# Main.net
KiCad netlist of a schematic drawn in EAGLE
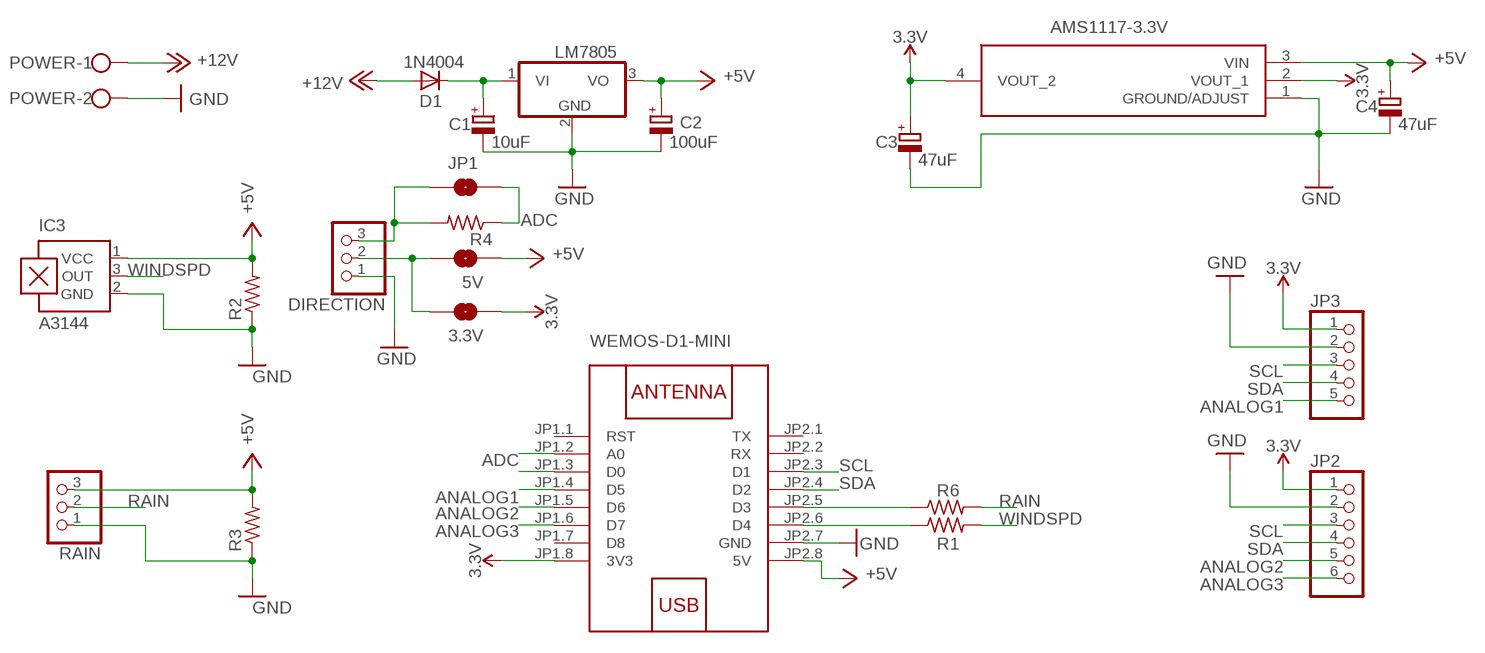
[diagram p0: schematic, sheet 1]

(export (version "E")
  (design (tool "Eeschema 10.0.6"))
  (components
    (comp (ref "3.3V")
      (value "JUMPER-SMT_2_NO_NO-SILK")
      (footprint "eagle-import:SMT-JUMPER_2_NO_NO-SILK")
      (libsource (lib "eagle-import") (part "JUMPER-SMT_2_NO_NO-SILK"))
    )
    (comp (ref "5V")
      (value "JUMPER-SMT_2_NO_NO-SILK")
      (footprint "eagle-import:SMT-JUMPER_2_NO_NO-SILK")
      (libsource (lib "eagle-import") (part "JUMPER-SMT_2_NO_NO-SILK"))
    )
    (comp (ref "C1")
      (value "10uF")
      (footprint "eagle-import:E2,5-5")
      (libsource (lib "eagle-import") (part "CPOL-EUE2.5-5"))
    )
    (comp (ref "C2")
      (value "100uF")
      (footprint "eagle-import:E2,5-5")
      (libsource (lib "eagle-import") (part "CPOL-EUE2.5-5"))
    )
    (comp (ref "C3")
      (value "47uF")
      (footprint "eagle-import:E2,5-5")
      (libsource (lib "eagle-import") (part "CPOL-EUE2.5-5"))
    )
    (comp (ref "C4")
      (value "47uF")
      (footprint "eagle-import:E2,5-5")
      (libsource (lib "eagle-import") (part "CPOL-EUE2.5-5"))
    )
    (comp (ref "D1")
      (value "1N4004")
      (footprint "eagle-import:DO41-10")
      (libsource (lib "eagle-import") (part "1N4004"))
    )
    (comp (ref "DIRECTION")
      (value "PINHD-1X3/90")
      (footprint "eagle-import:1X03_90")
      (libsource (lib "eagle-import") (part "PINHD-1X3/90"))
    )
    (comp (ref "IC1")
      (value "LM7805")
      (footprint "eagle-import:TO220H")
      (libsource (lib "eagle-import") (part "78T05"))
    )
    (comp (ref "IC2")
      (value "AMS1117-3.3V")
      (footprint "eagle-import:SOT229P700X180-4N")
      (fields (field (name "MANUFACTURER_PART_NUMBER") "ams1117-3.3v"))
      (libsource (lib "eagle-import") (part "AMS1117-3.3V"))
    )
    (comp (ref "IC3")
      (value "A3144")
      (footprint "eagle-import:SIP3-UA")
      (fields (field (name "MF") "ALLEGRO MICROSYSTEMS, INC.") (field (name "MPN") "A1301EUA-T"))
      (libsource (lib "eagle-import") (part "A13?UA01"))
    )
    (comp (ref "JP1")
      (value "JUMPER-SMT_2_NO_NO-SILK")
      (footprint "eagle-import:SMT-JUMPER_2_NO_NO-SILK")
      (libsource (lib "eagle-import") (part "JUMPER-SMT_2_NO_NO-SILK"))
    )
    (comp (ref "JP2")
      (value "PINHD-1X6/90")
      (footprint "eagle-import:1X06_90")
      (libsource (lib "eagle-import") (part "PINHD-1X6/90"))
    )
    (comp (ref "JP3")
      (value "PINHD-1X5/90")
      (footprint "eagle-import:1X05_90")
      (libsource (lib "eagle-import") (part "PINHD-1X5/90"))
    )
    (comp (ref "POWER")
      (value "W237-102")
      (footprint "eagle-import:W237-102")
      (fields (field (name "MPN") "237-102"))
      (libsource (lib "eagle-import") (part "W237-102"))
    )
    (comp (ref "R1")
      (value "R-US_0207/10")
      (footprint "eagle-import:0207_10")
      (libsource (lib "eagle-import") (part "R-US_0207/10"))
    )
    (comp (ref "R2")
      (value "R-US_0207/10")
      (footprint "eagle-import:0207_10")
      (libsource (lib "eagle-import") (part "R-US_0207/10"))
    )
    (comp (ref "R3")
      (value "R-US_0207/10")
      (footprint "eagle-import:0207_10")
      (libsource (lib "eagle-import") (part "R-US_0207/10"))
    )
    (comp (ref "R4")
      (value "R-US_0207/10")
      (footprint "eagle-import:0207_10")
      (libsource (lib "eagle-import") (part "R-US_0207/10"))
    )
    (comp (ref "R6")
      (value "R-US_0207/10")
      (footprint "eagle-import:0207_10")
      (libsource (lib "eagle-import") (part "R-US_0207/10"))
    )
    (comp (ref "RAIN")
      (value "PINHD-1X3/90")
      (footprint "eagle-import:1X03_90")
      (libsource (lib "eagle-import") (part "PINHD-1X3/90"))
    )
    (comp (ref "U$1")
      (value "WEMOS-D1-MINI")
      (footprint "eagle-import:WEMOS-D1-MINI")
      (libsource (lib "eagle-import") (part "WEMOS-D1-MINI"))
    )
  )
  (nets
    (net (code "1") (name "+5V") (class "Default")
      (node (ref "5V") (pin "1") (pinfunction "1_1") (pintype "passive"))
      (node (ref "C2") (pin "+") (pinfunction "+_+") (pintype "passive"))
      (node (ref "C4") (pin "+") (pinfunction "+_+") (pintype "passive"))
      (node (ref "IC1") (pin "3") (pinfunction "VO_3") (pintype "passive"))
      (node (ref "IC2") (pin "3") (pinfunction "VIN_3") (pintype "bidirectional"))
      (node (ref "IC3") (pin "1") (pinfunction "VCC_1") (pintype "power_in"))
      (node (ref "R2") (pin "2") (pinfunction "2_2") (pintype "passive"))
      (node (ref "R3") (pin "2") (pinfunction "2_2") (pintype "passive"))
      (node (ref "RAIN") (pin "3") (pinfunction "3_3") (pintype "passive"))
      (node (ref "U$1") (pin "JP2.8") (pinfunction "5V_JP2.8") (pintype "power_in"))
    )
    (net (code "2") (name "+12V") (class "Default")
      (node (ref "D1") (pin "A") (pinfunction "A_A") (pintype "passive"))
      (node (ref "POWER") (pin "1") (pinfunction "KL_1") (pintype "passive"))
    )
    (net (code "3") (name "/ADC") (class "Default")
      (node (ref "JP1") (pin "2") (pinfunction "2_2") (pintype "passive"))
      (node (ref "R4") (pin "1") (pinfunction "1_1") (pintype "passive"))
      (node (ref "U$1") (pin "JP1.2") (pinfunction "A0_JP1.2") (pintype "bidirectional"))
    )
    (net (code "4") (name "/ANALOG1") (class "Default")
      (node (ref "JP3") (pin "5") (pinfunction "5_5") (pintype "passive"))
      (node (ref "U$1") (pin "JP1.4") (pinfunction "D5_JP1.4") (pintype "bidirectional"))
    )
    (net (code "5") (name "/ANALOG2") (class "Default")
      (node (ref "JP2") (pin "5") (pinfunction "5_5") (pintype "passive"))
      (node (ref "U$1") (pin "JP1.5") (pinfunction "D6_JP1.5") (pintype "bidirectional"))
    )
    (net (code "6") (name "/ANALOG3") (class "Default")
      (node (ref "JP2") (pin "6") (pinfunction "6_6") (pintype "passive"))
      (node (ref "U$1") (pin "JP1.6") (pinfunction "D7_JP1.6") (pintype "bidirectional"))
    )
    (net (code "7") (name "/RAIN") (class "Default")
      (node (ref "R6") (pin "2") (pinfunction "2_2") (pintype "passive"))
      (node (ref "RAIN") (pin "2") (pinfunction "2_2") (pintype "passive"))
    )
    (net (code "8") (name "/SCL") (class "Default")
      (node (ref "JP2") (pin "3") (pinfunction "3_3") (pintype "passive"))
      (node (ref "JP3") (pin "3") (pinfunction "3_3") (pintype "passive"))
      (node (ref "U$1") (pin "JP2.3") (pinfunction "D1_JP2.3") (pintype "bidirectional"))
    )
    (net (code "9") (name "/SDA") (class "Default")
      (node (ref "JP2") (pin "4") (pinfunction "4_4") (pintype "passive"))
      (node (ref "JP3") (pin "4") (pinfunction "4_4") (pintype "passive"))
      (node (ref "U$1") (pin "JP2.4") (pinfunction "D2_JP2.4") (pintype "bidirectional"))
    )
    (net (code "10") (name "/WINDSPD") (class "Default")
      (node (ref "IC3") (pin "3") (pinfunction "OUT_3") (pintype "output"))
      (node (ref "R1") (pin "2") (pinfunction "2_2") (pintype "passive"))
    )
    (net (code "11") (name "3.3V") (class "Default")
      (node (ref "3.3V") (pin "1") (pinfunction "1_1") (pintype "passive"))
      (node (ref "C3") (pin "+") (pinfunction "+_+") (pintype "passive"))
      (node (ref "IC2") (pin "2") (pinfunction "VOUT_1_2") (pintype "bidirectional"))
      (node (ref "IC2") (pin "4") (pinfunction "VOUT_2_4") (pintype "bidirectional"))
      (node (ref "JP2") (pin "1") (pinfunction "1_1") (pintype "passive"))
      (node (ref "JP3") (pin "1") (pinfunction "1_1") (pintype "passive"))
      (node (ref "U$1") (pin "JP1.8") (pinfunction "3V3_JP1.8") (pintype "power_in"))
    )
    (net (code "12") (name "GND") (class "Default")
      (node (ref "C1") (pin "-") (pinfunction "-_-") (pintype "passive"))
      (node (ref "C2") (pin "-") (pinfunction "-_-") (pintype "passive"))
      (node (ref "C3") (pin "-") (pinfunction "-_-") (pintype "passive"))
      (node (ref "C4") (pin "-") (pinfunction "-_-") (pintype "passive"))
      (node (ref "DIRECTION") (pin "1") (pinfunction "1_1") (pintype "passive"))
      (node (ref "IC1") (pin "2") (pinfunction "GND_2") (pintype "passive"))
      (node (ref "IC2") (pin "1") (pinfunction "GROUND/ADJUST_1") (pintype "bidirectional"))
      (node (ref "IC3") (pin "2") (pinfunction "GND_2") (pintype "power_in"))
      (node (ref "JP2") (pin "2") (pinfunction "2_2") (pintype "passive"))
      (node (ref "JP3") (pin "2") (pinfunction "2_2") (pintype "passive"))
      (node (ref "POWER") (pin "2") (pinfunction "KL_2") (pintype "passive"))
      (node (ref "R2") (pin "1") (pinfunction "1_1") (pintype "passive"))
      (node (ref "R3") (pin "1") (pinfunction "1_1") (pintype "passive"))
      (node (ref "RAIN") (pin "1") (pinfunction "1_1") (pintype "passive"))
      (node (ref "U$1") (pin "JP2.7") (pinfunction "GND_JP2.7") (pintype "power_in"))
    )
    (net (code "13") (name "Net-(3.3V-Pad2)") (class "Default")
      (node (ref "3.3V") (pin "2") (pinfunction "2_2") (pintype "passive"))
      (node (ref "5V") (pin "2") (pinfunction "2_2") (pintype "passive"))
      (node (ref "DIRECTION") (pin "2") (pinfunction "2_2") (pintype "passive"))
    )
    (net (code "14") (name "Net-(DIRECTION-Pad3)") (class "Default")
      (node (ref "DIRECTION") (pin "3") (pinfunction "3_3") (pintype "passive"))
      (node (ref "JP1") (pin "1") (pinfunction "1_1") (pintype "passive"))
      (node (ref "R4") (pin "2") (pinfunction "2_2") (pintype "passive"))
    )
    (net (code "15") (name "Net-(IC1-VI)") (class "Default")
      (node (ref "C1") (pin "+") (pinfunction "+_+") (pintype "passive"))
      (node (ref "D1") (pin "C") (pinfunction "C_C") (pintype "passive"))
      (node (ref "IC1") (pin "1") (pinfunction "VI_1") (pintype "input"))
    )
    (net (code "16") (name "Net-(U$1-D3)") (class "Default")
      (node (ref "R6") (pin "1") (pinfunction "1_1") (pintype "passive"))
      (node (ref "U$1") (pin "JP2.5") (pinfunction "D3_JP2.5") (pintype "bidirectional"))
    )
    (net (code "17") (name "Net-(U$1-D4)") (class "Default")
      (node (ref "R1") (pin "1") (pinfunction "1_1") (pintype "passive"))
      (node (ref "U$1") (pin "JP2.6") (pinfunction "D4_JP2.6") (pintype "bidirectional"))
    )
    (net (code "18") (name "unconnected-(U$1-D0-PadJP1.3)") (class "Default")
      (node (ref "U$1") (pin "JP1.3") (pinfunction "D0_JP1.3") (pintype "bidirectional"))
    )
    (net (code "19") (name "unconnected-(U$1-D8-PadJP1.7)") (class "Default")
      (node (ref "U$1") (pin "JP1.7") (pinfunction "D8_JP1.7") (pintype "bidirectional"))
    )
    (net (code "20") (name "unconnected-(U$1-RST-PadJP1.1)") (class "Default")
      (node (ref "U$1") (pin "JP1.1") (pinfunction "RST_JP1.1") (pintype "bidirectional"))
    )
    (net (code "21") (name "unconnected-(U$1-RX-PadJP2.2)") (class "Default")
      (node (ref "U$1") (pin "JP2.2") (pinfunction "RX_JP2.2") (pintype "bidirectional"))
    )
    (net (code "22") (name "unconnected-(U$1-TX-PadJP2.1)") (class "Default")
      (node (ref "U$1") (pin "JP2.1") (pinfunction "TX_JP2.1") (pintype "bidirectional"))
    )
  )
)
